# B602A.net
KiCad netlist of a schematic drawn in EAGLE
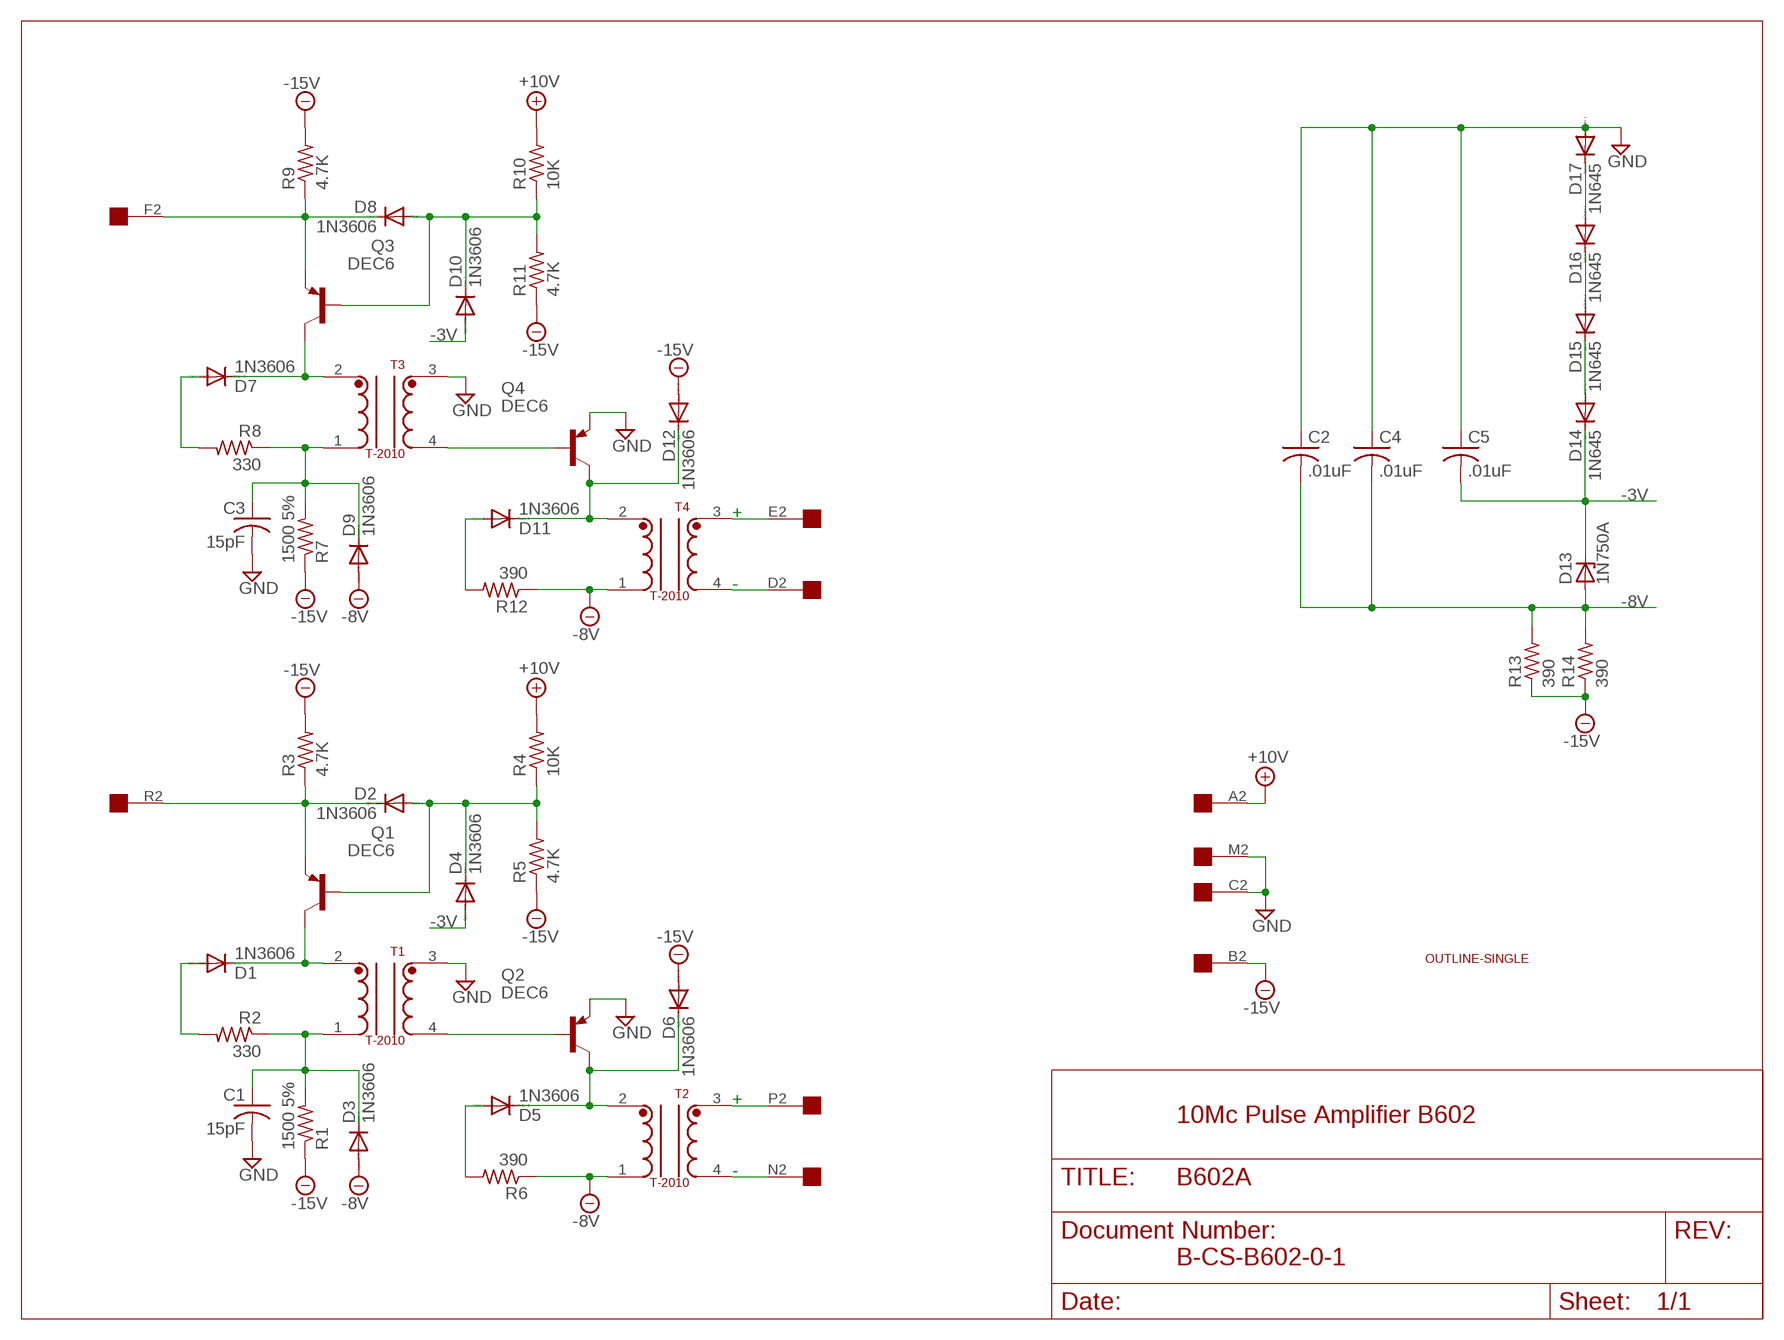
[diagram p0: schematic, sheet 1]

(export (version "E")
  (design (tool "Eeschema 10.0.6"))
  (components
    (comp (ref "C1")
      (value "15pF")
      (footprint "eagle-import:C050-025X075")
      (libsource (lib "eagle-import") (part "C-US050-025X075"))
    )
    (comp (ref "C2")
      (value ".01uF")
      (footprint "eagle-import:C050-025X075")
      (libsource (lib "eagle-import") (part "C-US050-025X075"))
    )
    (comp (ref "C3")
      (value "15pF")
      (footprint "eagle-import:C050-025X075")
      (libsource (lib "eagle-import") (part "C-US050-025X075"))
    )
    (comp (ref "C4")
      (value ".01uF")
      (footprint "eagle-import:C050-025X075")
      (libsource (lib "eagle-import") (part "C-US050-025X075"))
    )
    (comp (ref "C5")
      (value ".01uF")
      (footprint "eagle-import:C050-025X075")
      (libsource (lib "eagle-import") (part "C-US050-025X075"))
    )
    (comp (ref "D1")
      (value "1N3606")
      (footprint "eagle-import:DO35-10")
      (libsource (lib "eagle-import") (part "1N4148DO35-10"))
    )
    (comp (ref "D2")
      (value "1N3606")
      (footprint "eagle-import:DO35-10")
      (libsource (lib "eagle-import") (part "1N4148DO35-10"))
    )
    (comp (ref "D3")
      (value "1N3606")
      (footprint "eagle-import:DO35-10")
      (libsource (lib "eagle-import") (part "1N4148DO35-10"))
    )
    (comp (ref "D4")
      (value "1N3606")
      (footprint "eagle-import:DO35-10")
      (libsource (lib "eagle-import") (part "1N4148DO35-10"))
    )
    (comp (ref "D5")
      (value "1N3606")
      (footprint "eagle-import:DO35-10")
      (libsource (lib "eagle-import") (part "1N4148DO35-10"))
    )
    (comp (ref "D6")
      (value "1N3606")
      (footprint "eagle-import:DO35-10")
      (libsource (lib "eagle-import") (part "1N4148DO35-10"))
    )
    (comp (ref "D7")
      (value "1N3606")
      (footprint "eagle-import:DO35-10")
      (libsource (lib "eagle-import") (part "1N4148DO35-10"))
    )
    (comp (ref "D8")
      (value "1N3606")
      (footprint "eagle-import:DO35-10")
      (libsource (lib "eagle-import") (part "1N4148DO35-10"))
    )
    (comp (ref "D9")
      (value "1N3606")
      (footprint "eagle-import:DO35-10")
      (libsource (lib "eagle-import") (part "1N4148DO35-10"))
    )
    (comp (ref "D10")
      (value "1N3606")
      (footprint "eagle-import:DO35-10")
      (libsource (lib "eagle-import") (part "1N4148DO35-10"))
    )
    (comp (ref "D11")
      (value "1N3606")
      (footprint "eagle-import:DO35-10")
      (libsource (lib "eagle-import") (part "1N4148DO35-10"))
    )
    (comp (ref "D12")
      (value "1N3606")
      (footprint "eagle-import:DO35-10")
      (libsource (lib "eagle-import") (part "1N4148DO35-10"))
    )
    (comp (ref "D13")
      (value "1N750A")
      (footprint "eagle-import:DO35Z10")
      (libsource (lib "eagle-import") (part "ZENER-DIODEDO35Z10"))
    )
    (comp (ref "D14")
      (value "1N645")
      (footprint "eagle-import:DO35-10")
      (libsource (lib "eagle-import") (part "1N4148DO35-10"))
    )
    (comp (ref "D15")
      (value "1N645")
      (footprint "eagle-import:DO35-10")
      (libsource (lib "eagle-import") (part "1N4148DO35-10"))
    )
    (comp (ref "D16")
      (value "1N645")
      (footprint "eagle-import:DO35-10")
      (libsource (lib "eagle-import") (part "1N4148DO35-10"))
    )
    (comp (ref "D17")
      (value "1N645")
      (footprint "eagle-import:DO35-10")
      (libsource (lib "eagle-import") (part "1N4148DO35-10"))
    )
    (comp (ref "Q1")
      (value "DEC6")
      (footprint "eagle-import:TO39")
      (libsource (lib "eagle-import") (part "2N2904"))
    )
    (comp (ref "Q2")
      (value "DEC6")
      (footprint "eagle-import:TO39")
      (libsource (lib "eagle-import") (part "2N2904"))
    )
    (comp (ref "Q3")
      (value "DEC6")
      (footprint "eagle-import:TO39")
      (libsource (lib "eagle-import") (part "2N2904"))
    )
    (comp (ref "Q4")
      (value "DEC6")
      (footprint "eagle-import:TO39")
      (libsource (lib "eagle-import") (part "2N2904"))
    )
    (comp (ref "R1")
      (value "1500 5%")
      (footprint "eagle-import:0207_10")
      (libsource (lib "eagle-import") (part "R-US_0207/10"))
    )
    (comp (ref "R2")
      (value "330")
      (footprint "eagle-import:0207_10")
      (libsource (lib "eagle-import") (part "R-US_0207/10"))
    )
    (comp (ref "R3")
      (value "4.7K")
      (footprint "eagle-import:0207_10")
      (libsource (lib "eagle-import") (part "R-US_0207/10"))
    )
    (comp (ref "R4")
      (value "10K")
      (footprint "eagle-import:0207_10")
      (libsource (lib "eagle-import") (part "R-US_0207/10"))
    )
    (comp (ref "R5")
      (value "4.7K")
      (footprint "eagle-import:0207_10")
      (libsource (lib "eagle-import") (part "R-US_0207/10"))
    )
    (comp (ref "R6")
      (value "390")
      (footprint "eagle-import:0207_10")
      (libsource (lib "eagle-import") (part "R-US_0207/10"))
    )
    (comp (ref "R7")
      (value "1500 5%")
      (footprint "eagle-import:0207_10")
      (libsource (lib "eagle-import") (part "R-US_0207/10"))
    )
    (comp (ref "R8")
      (value "330")
      (footprint "eagle-import:0207_10")
      (libsource (lib "eagle-import") (part "R-US_0207/10"))
    )
    (comp (ref "R9")
      (value "4.7K")
      (footprint "eagle-import:0207_10")
      (libsource (lib "eagle-import") (part "R-US_0207/10"))
    )
    (comp (ref "R10")
      (value "10K")
      (footprint "eagle-import:0207_10")
      (libsource (lib "eagle-import") (part "R-US_0207/10"))
    )
    (comp (ref "R11")
      (value "4.7K")
      (footprint "eagle-import:0207_10")
      (libsource (lib "eagle-import") (part "R-US_0207/10"))
    )
    (comp (ref "R12")
      (value "390")
      (footprint "eagle-import:0207_10")
      (libsource (lib "eagle-import") (part "R-US_0207/10"))
    )
    (comp (ref "R13")
      (value "390")
      (footprint "eagle-import:0207_10")
      (libsource (lib "eagle-import") (part "R-US_0207/10"))
    )
    (comp (ref "R14")
      (value "390")
      (footprint "eagle-import:0207_10")
      (libsource (lib "eagle-import") (part "R-US_0207/10"))
    )
    (comp (ref "T1")
      (value "T-2010")
      (footprint "eagle-import:TRANSFORMER2")
      (libsource (lib "eagle-import") (part "T-2010"))
    )
    (comp (ref "T2")
      (value "T-2010")
      (footprint "eagle-import:TRANSFORMER2")
      (libsource (lib "eagle-import") (part "T-2010"))
    )
    (comp (ref "T3")
      (value "T-2010")
      (footprint "eagle-import:TRANSFORMER2")
      (libsource (lib "eagle-import") (part "T-2010"))
    )
    (comp (ref "T4")
      (value "T-2010")
      (footprint "eagle-import:TRANSFORMER2")
      (libsource (lib "eagle-import") (part "T-2010"))
    )
    (comp (ref "U$1")
      (value "OUTLINE-SINGLE")
      (footprint "eagle-import:SINGLE")
      (libsource (lib "eagle-import") (part "OUTLINE-SINGLE"))
    )
    (comp (ref "U$2")
      (value "EDGE-1")
      (footprint "eagle-import:EDGE-CON1")
      (libsource (lib "eagle-import") (part "EDGE-1"))
    )
  )
  (nets
    (net (code "1") (name "+10V") (class "Default")
      (node (ref "R10") (pin "2") (pinfunction "2_2") (pintype "passive"))
      (node (ref "R4") (pin "2") (pinfunction "2_2") (pintype "passive"))
      (node (ref "U$2") (pin "A2") (pinfunction "1_A2") (pintype "bidirectional"))
    )
    (net (code "2") (name "-8V") (class "Default")
      (node (ref "C2") (pin "2") (pinfunction "2_2") (pintype "passive"))
      (node (ref "C4") (pin "2") (pinfunction "2_2") (pintype "passive"))
      (node (ref "D13") (pin "A") (pinfunction "A_A") (pintype "passive"))
      (node (ref "D3") (pin "A") (pinfunction "A_A") (pintype "passive"))
      (node (ref "D9") (pin "A") (pinfunction "A_A") (pintype "passive"))
      (node (ref "R12") (pin "1") (pinfunction "1_1") (pintype "passive"))
      (node (ref "R13") (pin "2") (pinfunction "2_2") (pintype "passive"))
      (node (ref "R14") (pin "2") (pinfunction "2_2") (pintype "passive"))
      (node (ref "R6") (pin "1") (pinfunction "1_1") (pintype "passive"))
      (node (ref "T2") (pin "1") (pinfunction "P$5_1") (pintype "passive"))
      (node (ref "T4") (pin "1") (pinfunction "P$5_1") (pintype "passive"))
    )
    (net (code "3") (name "-15V") (class "Default")
      (node (ref "D12") (pin "A") (pinfunction "A_A") (pintype "passive"))
      (node (ref "D6") (pin "A") (pinfunction "A_A") (pintype "passive"))
      (node (ref "R1") (pin "1") (pinfunction "1_1") (pintype "passive"))
      (node (ref "R11") (pin "1") (pinfunction "1_1") (pintype "passive"))
      (node (ref "R13") (pin "1") (pinfunction "1_1") (pintype "passive"))
      (node (ref "R14") (pin "1") (pinfunction "1_1") (pintype "passive"))
      (node (ref "R3") (pin "2") (pinfunction "2_2") (pintype "passive"))
      (node (ref "R5") (pin "1") (pinfunction "1_1") (pintype "passive"))
      (node (ref "R7") (pin "1") (pinfunction "1_1") (pintype "passive"))
      (node (ref "R9") (pin "2") (pinfunction "2_2") (pintype "passive"))
      (node (ref "U$2") (pin "B2") (pinfunction "1_B2") (pintype "bidirectional"))
    )
    (net (code "4") (name "/-3V") (class "Default")
      (node (ref "C5") (pin "2") (pinfunction "2_2") (pintype "passive"))
      (node (ref "D10") (pin "A") (pinfunction "A_A") (pintype "passive"))
      (node (ref "D13") (pin "C") (pinfunction "C_C") (pintype "passive"))
      (node (ref "D14") (pin "C") (pinfunction "C_C") (pintype "passive"))
      (node (ref "D4") (pin "A") (pinfunction "A_A") (pintype "passive"))
    )
    (net (code "5") (name "GND") (class "Default")
      (node (ref "C1") (pin "2") (pinfunction "2_2") (pintype "passive"))
      (node (ref "C2") (pin "1") (pinfunction "1_1") (pintype "passive"))
      (node (ref "C3") (pin "2") (pinfunction "2_2") (pintype "passive"))
      (node (ref "C4") (pin "1") (pinfunction "1_1") (pintype "passive"))
      (node (ref "C5") (pin "1") (pinfunction "1_1") (pintype "passive"))
      (node (ref "D17") (pin "A") (pinfunction "A_A") (pintype "passive"))
      (node (ref "Q2") (pin "1") (pinfunction "E_1") (pintype "passive"))
      (node (ref "Q4") (pin "1") (pinfunction "E_1") (pintype "passive"))
      (node (ref "T1") (pin "3") (pinfunction "P$2_3") (pintype "passive"))
      (node (ref "T3") (pin "3") (pinfunction "P$2_3") (pintype "passive"))
      (node (ref "U$2") (pin "C2") (pinfunction "1_C2") (pintype "bidirectional"))
      (node (ref "U$2") (pin "M2") (pinfunction "1_M2") (pintype "bidirectional"))
    )
    (net (code "6") (name "Net-(D1-PadA)") (class "Default")
      (node (ref "D1") (pin "A") (pinfunction "A_A") (pintype "passive"))
      (node (ref "R2") (pin "2") (pinfunction "2_2") (pintype "passive"))
    )
    (net (code "7") (name "Net-(D5-PadA)") (class "Default")
      (node (ref "D5") (pin "A") (pinfunction "A_A") (pintype "passive"))
      (node (ref "R6") (pin "2") (pinfunction "2_2") (pintype "passive"))
    )
    (net (code "8") (name "Net-(D7-PadA)") (class "Default")
      (node (ref "D7") (pin "A") (pinfunction "A_A") (pintype "passive"))
      (node (ref "R8") (pin "2") (pinfunction "2_2") (pintype "passive"))
    )
    (net (code "9") (name "Net-(D11-PadA)") (class "Default")
      (node (ref "D11") (pin "A") (pinfunction "A_A") (pintype "passive"))
      (node (ref "R12") (pin "2") (pinfunction "2_2") (pintype "passive"))
    )
    (net (code "10") (name "Net-(D14-PadA)") (class "Default")
      (node (ref "D14") (pin "A") (pinfunction "A_A") (pintype "passive"))
      (node (ref "D15") (pin "C") (pinfunction "C_C") (pintype "passive"))
    )
    (net (code "11") (name "Net-(D15-PadA)") (class "Default")
      (node (ref "D15") (pin "A") (pinfunction "A_A") (pintype "passive"))
      (node (ref "D16") (pin "C") (pinfunction "C_C") (pintype "passive"))
    )
    (net (code "12") (name "Net-(D16-PadA)") (class "Default")
      (node (ref "D16") (pin "A") (pinfunction "A_A") (pintype "passive"))
      (node (ref "D17") (pin "C") (pinfunction "C_C") (pintype "passive"))
    )
    (net (code "13") (name "Net-(Q1-B)") (class "Default")
      (node (ref "D2") (pin "A") (pinfunction "A_A") (pintype "passive"))
      (node (ref "D4") (pin "C") (pinfunction "C_C") (pintype "passive"))
      (node (ref "Q1") (pin "2") (pinfunction "B_2") (pintype "passive"))
      (node (ref "R4") (pin "1") (pinfunction "1_1") (pintype "passive"))
      (node (ref "R5") (pin "2") (pinfunction "2_2") (pintype "passive"))
    )
    (net (code "14") (name "Net-(Q1-C)") (class "Default")
      (node (ref "D1") (pin "C") (pinfunction "C_C") (pintype "passive"))
      (node (ref "Q1") (pin "3") (pinfunction "C_3") (pintype "passive"))
      (node (ref "T1") (pin "2") (pinfunction "P$4_2") (pintype "passive"))
    )
    (net (code "15") (name "Net-(Q1-E)") (class "Default")
      (node (ref "D2") (pin "C") (pinfunction "C_C") (pintype "passive"))
      (node (ref "Q1") (pin "1") (pinfunction "E_1") (pintype "passive"))
      (node (ref "R3") (pin "1") (pinfunction "1_1") (pintype "passive"))
      (node (ref "U$2") (pin "R2") (pinfunction "1_R2") (pintype "bidirectional"))
    )
    (net (code "16") (name "Net-(Q2-B)") (class "Default")
      (node (ref "Q2") (pin "2") (pinfunction "B_2") (pintype "passive"))
      (node (ref "T1") (pin "4") (pinfunction "P$7_4") (pintype "passive"))
    )
    (net (code "17") (name "Net-(Q2-C)") (class "Default")
      (node (ref "D5") (pin "C") (pinfunction "C_C") (pintype "passive"))
      (node (ref "D6") (pin "C") (pinfunction "C_C") (pintype "passive"))
      (node (ref "Q2") (pin "3") (pinfunction "C_3") (pintype "passive"))
      (node (ref "T2") (pin "2") (pinfunction "P$4_2") (pintype "passive"))
    )
    (net (code "18") (name "Net-(Q3-B)") (class "Default")
      (node (ref "D10") (pin "C") (pinfunction "C_C") (pintype "passive"))
      (node (ref "D8") (pin "A") (pinfunction "A_A") (pintype "passive"))
      (node (ref "Q3") (pin "2") (pinfunction "B_2") (pintype "passive"))
      (node (ref "R10") (pin "1") (pinfunction "1_1") (pintype "passive"))
      (node (ref "R11") (pin "2") (pinfunction "2_2") (pintype "passive"))
    )
    (net (code "19") (name "Net-(Q3-C)") (class "Default")
      (node (ref "D7") (pin "C") (pinfunction "C_C") (pintype "passive"))
      (node (ref "Q3") (pin "3") (pinfunction "C_3") (pintype "passive"))
      (node (ref "T3") (pin "2") (pinfunction "P$4_2") (pintype "passive"))
    )
    (net (code "20") (name "Net-(Q3-E)") (class "Default")
      (node (ref "D8") (pin "C") (pinfunction "C_C") (pintype "passive"))
      (node (ref "Q3") (pin "1") (pinfunction "E_1") (pintype "passive"))
      (node (ref "R9") (pin "1") (pinfunction "1_1") (pintype "passive"))
      (node (ref "U$2") (pin "F2") (pinfunction "1_F2") (pintype "bidirectional"))
    )
    (net (code "21") (name "Net-(Q4-B)") (class "Default")
      (node (ref "Q4") (pin "2") (pinfunction "B_2") (pintype "passive"))
      (node (ref "T3") (pin "4") (pinfunction "P$7_4") (pintype "passive"))
    )
    (net (code "22") (name "Net-(Q4-C)") (class "Default")
      (node (ref "D11") (pin "C") (pinfunction "C_C") (pintype "passive"))
      (node (ref "D12") (pin "C") (pinfunction "C_C") (pintype "passive"))
      (node (ref "Q4") (pin "3") (pinfunction "C_3") (pintype "passive"))
      (node (ref "T4") (pin "2") (pinfunction "P$4_2") (pintype "passive"))
    )
    (net (code "23") (name "Net-(T1-P$5)") (class "Default")
      (node (ref "C1") (pin "1") (pinfunction "1_1") (pintype "passive"))
      (node (ref "D3") (pin "C") (pinfunction "C_C") (pintype "passive"))
      (node (ref "R1") (pin "2") (pinfunction "2_2") (pintype "passive"))
      (node (ref "R2") (pin "1") (pinfunction "1_1") (pintype "passive"))
      (node (ref "T1") (pin "1") (pinfunction "P$5_1") (pintype "passive"))
    )
    (net (code "24") (name "Net-(T2-P$2)") (class "Default")
      (node (ref "T2") (pin "3") (pinfunction "P$2_3") (pintype "passive"))
      (node (ref "U$2") (pin "P2") (pinfunction "1_P2") (pintype "bidirectional"))
    )
    (net (code "25") (name "Net-(T2-P$7)") (class "Default")
      (node (ref "T2") (pin "4") (pinfunction "P$7_4") (pintype "passive"))
      (node (ref "U$2") (pin "N2") (pinfunction "1_N2") (pintype "bidirectional"))
    )
    (net (code "26") (name "Net-(T3-P$5)") (class "Default")
      (node (ref "C3") (pin "1") (pinfunction "1_1") (pintype "passive"))
      (node (ref "D9") (pin "C") (pinfunction "C_C") (pintype "passive"))
      (node (ref "R7") (pin "2") (pinfunction "2_2") (pintype "passive"))
      (node (ref "R8") (pin "1") (pinfunction "1_1") (pintype "passive"))
      (node (ref "T3") (pin "1") (pinfunction "P$5_1") (pintype "passive"))
    )
    (net (code "27") (name "Net-(T4-P$2)") (class "Default")
      (node (ref "T4") (pin "3") (pinfunction "P$2_3") (pintype "passive"))
      (node (ref "U$2") (pin "E2") (pinfunction "1_E2") (pintype "bidirectional"))
    )
    (net (code "28") (name "Net-(T4-P$7)") (class "Default")
      (node (ref "T4") (pin "4") (pinfunction "P$7_4") (pintype "passive"))
      (node (ref "U$2") (pin "D2") (pinfunction "1_D2") (pintype "bidirectional"))
    )
  )
)
